# mister_case_top.net
KiCad netlist of a schematic drawn in EAGLE
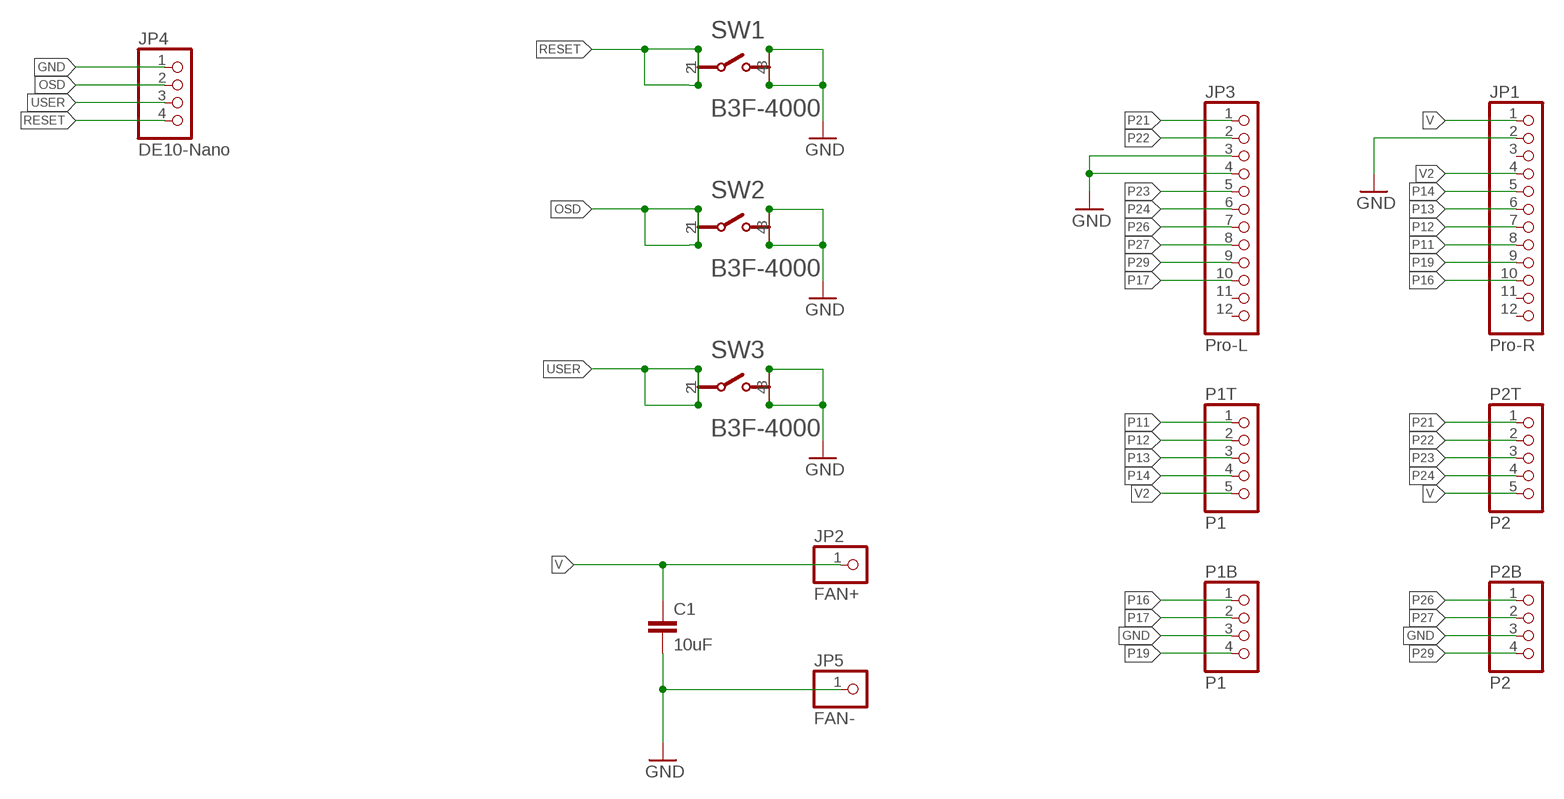
[diagram p0: schematic, sheet 1]

(export (version "E")
  (design (tool "Eeschema 10.0.6"))
  (components
    (comp (ref "C1")
      (value "10uF")
      (footprint "eagle-import:C0805")
      (libsource (lib "eagle-import") (part "C-EUC0805"))
    )
    (comp (ref "JP1")
      (value "Pro-R")
      (footprint "eagle-import:1X12L-NOHOLES")
      (libsource (lib "eagle-import") (part "PINHD-1X12-NOHOLESNOHOLES"))
    )
    (comp (ref "JP2")
      (value "FAN+")
      (footprint "eagle-import:1X01")
      (libsource (lib "eagle-import") (part "PINHD-1X1"))
    )
    (comp (ref "JP3")
      (value "Pro-L")
      (footprint "eagle-import:1X12L-NOHOLES")
      (libsource (lib "eagle-import") (part "PINHD-1X12-NOHOLESNOHOLES"))
    )
    (comp (ref "JP4")
      (value "DE10-Nano")
      (footprint "eagle-import:1X04")
      (libsource (lib "eagle-import") (part "PINHD-1X4"))
    )
    (comp (ref "JP5")
      (value "FAN-")
      (footprint "eagle-import:1X01")
      (libsource (lib "eagle-import") (part "PINHD-1X1"))
    )
    (comp (ref "P1B")
      (value "P1")
      (footprint "eagle-import:1X04")
      (libsource (lib "eagle-import") (part "pinhead_325_PINHD-1X4"))
    )
    (comp (ref "P1T")
      (value "P1")
      (footprint "eagle-import:1X05")
      (libsource (lib "eagle-import") (part "PINHD-1X5"))
    )
    (comp (ref "P2B")
      (value "P2")
      (footprint "eagle-import:1X04")
      (libsource (lib "eagle-import") (part "pinhead_325_PINHD-1X4"))
    )
    (comp (ref "P2T")
      (value "P2")
      (footprint "eagle-import:1X05")
      (libsource (lib "eagle-import") (part "PINHD-1X5"))
    )
    (comp (ref "SW1")
      (value "OMRON_B3F-4000")
      (footprint "eagle-import:OMRON_B3F-4000_NOHOLES")
      (libsource (lib "eagle-import") (part "OMRON_B3F-4000"))
    )
    (comp (ref "SW2")
      (value "OMRON_B3F-4000")
      (footprint "eagle-import:OMRON_B3F-4000_NOHOLES")
      (libsource (lib "eagle-import") (part "OMRON_B3F-4000"))
    )
    (comp (ref "SW3")
      (value "OMRON_B3F-4000")
      (footprint "eagle-import:OMRON_B3F-4000_NOHOLES")
      (libsource (lib "eagle-import") (part "OMRON_B3F-4000"))
    )
  )
  (nets
    (net (code "1") (name "GND") (class "Default")
      (node (ref "C1") (pin "2") (pinfunction "2_2") (pintype "passive"))
      (node (ref "JP1") (pin "2") (pinfunction "2_2") (pintype "passive"))
      (node (ref "JP3") (pin "3") (pinfunction "3_3") (pintype "passive"))
      (node (ref "JP3") (pin "4") (pinfunction "4_4") (pintype "passive"))
      (node (ref "JP4") (pin "1") (pinfunction "1_1") (pintype "passive"))
      (node (ref "JP5") (pin "1") (pinfunction "1_1") (pintype "passive"))
      (node (ref "P1B") (pin "3") (pinfunction "3_3") (pintype "passive"))
      (node (ref "P2B") (pin "3") (pinfunction "3_3") (pintype "passive"))
      (node (ref "SW1") (pin "3") (pinfunction "3_3") (pintype "passive"))
      (node (ref "SW1") (pin "4") (pinfunction "4_4") (pintype "passive"))
      (node (ref "SW2") (pin "3") (pinfunction "3_3") (pintype "passive"))
      (node (ref "SW2") (pin "4") (pinfunction "4_4") (pintype "passive"))
      (node (ref "SW3") (pin "3") (pinfunction "3_3") (pintype "passive"))
      (node (ref "SW3") (pin "4") (pinfunction "4_4") (pintype "passive"))
    )
    (net (code "2") (name "OSD") (class "Default")
      (node (ref "JP4") (pin "2") (pinfunction "2_2") (pintype "passive"))
      (node (ref "SW2") (pin "1") (pinfunction "1_1") (pintype "passive"))
      (node (ref "SW2") (pin "2") (pinfunction "2_2") (pintype "passive"))
    )
    (net (code "3") (name "P11") (class "Default")
      (node (ref "JP1") (pin "8") (pinfunction "8_8") (pintype "passive"))
      (node (ref "P1T") (pin "1") (pinfunction "1_1") (pintype "passive"))
    )
    (net (code "4") (name "P12") (class "Default")
      (node (ref "JP1") (pin "7") (pinfunction "7_7") (pintype "passive"))
      (node (ref "P1T") (pin "2") (pinfunction "2_2") (pintype "passive"))
    )
    (net (code "5") (name "P13") (class "Default")
      (node (ref "JP1") (pin "6") (pinfunction "6_6") (pintype "passive"))
      (node (ref "P1T") (pin "3") (pinfunction "3_3") (pintype "passive"))
    )
    (net (code "6") (name "P14") (class "Default")
      (node (ref "JP1") (pin "5") (pinfunction "5_5") (pintype "passive"))
      (node (ref "P1T") (pin "4") (pinfunction "4_4") (pintype "passive"))
    )
    (net (code "7") (name "P16") (class "Default")
      (node (ref "JP1") (pin "10") (pinfunction "10_10") (pintype "passive"))
      (node (ref "P1B") (pin "1") (pinfunction "1_1") (pintype "passive"))
    )
    (net (code "8") (name "P17") (class "Default")
      (node (ref "JP3") (pin "10") (pinfunction "10_10") (pintype "passive"))
      (node (ref "P1B") (pin "2") (pinfunction "2_2") (pintype "passive"))
    )
    (net (code "9") (name "P19") (class "Default")
      (node (ref "JP1") (pin "9") (pinfunction "9_9") (pintype "passive"))
      (node (ref "P1B") (pin "4") (pinfunction "4_4") (pintype "passive"))
    )
    (net (code "10") (name "P21") (class "Default")
      (node (ref "JP3") (pin "1") (pinfunction "1_1") (pintype "passive"))
      (node (ref "P2T") (pin "1") (pinfunction "1_1") (pintype "passive"))
    )
    (net (code "11") (name "P22") (class "Default")
      (node (ref "JP3") (pin "2") (pinfunction "2_2") (pintype "passive"))
      (node (ref "P2T") (pin "2") (pinfunction "2_2") (pintype "passive"))
    )
    (net (code "12") (name "P23") (class "Default")
      (node (ref "JP3") (pin "5") (pinfunction "5_5") (pintype "passive"))
      (node (ref "P2T") (pin "3") (pinfunction "3_3") (pintype "passive"))
    )
    (net (code "13") (name "P24") (class "Default")
      (node (ref "JP3") (pin "6") (pinfunction "6_6") (pintype "passive"))
      (node (ref "P2T") (pin "4") (pinfunction "4_4") (pintype "passive"))
    )
    (net (code "14") (name "P26") (class "Default")
      (node (ref "JP3") (pin "7") (pinfunction "7_7") (pintype "passive"))
      (node (ref "P2B") (pin "1") (pinfunction "1_1") (pintype "passive"))
    )
    (net (code "15") (name "P27") (class "Default")
      (node (ref "JP3") (pin "8") (pinfunction "8_8") (pintype "passive"))
      (node (ref "P2B") (pin "2") (pinfunction "2_2") (pintype "passive"))
    )
    (net (code "16") (name "P29") (class "Default")
      (node (ref "JP3") (pin "9") (pinfunction "9_9") (pintype "passive"))
      (node (ref "P2B") (pin "4") (pinfunction "4_4") (pintype "passive"))
    )
    (net (code "17") (name "RESET") (class "Default")
      (node (ref "JP4") (pin "4") (pinfunction "4_4") (pintype "passive"))
      (node (ref "SW1") (pin "1") (pinfunction "1_1") (pintype "passive"))
      (node (ref "SW1") (pin "2") (pinfunction "2_2") (pintype "passive"))
    )
    (net (code "18") (name "USER") (class "Default")
      (node (ref "JP4") (pin "3") (pinfunction "3_3") (pintype "passive"))
      (node (ref "SW3") (pin "1") (pinfunction "1_1") (pintype "passive"))
      (node (ref "SW3") (pin "2") (pinfunction "2_2") (pintype "passive"))
    )
    (net (code "19") (name "V") (class "Default")
      (node (ref "C1") (pin "1") (pinfunction "1_1") (pintype "passive"))
      (node (ref "JP1") (pin "1") (pinfunction "1_1") (pintype "passive"))
      (node (ref "JP2") (pin "1") (pinfunction "1_1") (pintype "passive"))
      (node (ref "P2T") (pin "5") (pinfunction "5_5") (pintype "passive"))
    )
    (net (code "20") (name "V2") (class "Default")
      (node (ref "JP1") (pin "4") (pinfunction "4_4") (pintype "passive"))
      (node (ref "P1T") (pin "5") (pinfunction "5_5") (pintype "passive"))
    )
    (net (code "21") (name "unconnected-(JP1-Pad3)") (class "Default")
      (node (ref "JP1") (pin "3") (pinfunction "3_3") (pintype "passive"))
    )
    (net (code "22") (name "unconnected-(JP1-Pad11)") (class "Default")
      (node (ref "JP1") (pin "11") (pinfunction "11_11") (pintype "passive"))
    )
    (net (code "23") (name "unconnected-(JP1-Pad12)") (class "Default")
      (node (ref "JP1") (pin "12") (pinfunction "12_12") (pintype "passive"))
    )
    (net (code "24") (name "unconnected-(JP3-Pad11)") (class "Default")
      (node (ref "JP3") (pin "11") (pinfunction "11_11") (pintype "passive"))
    )
    (net (code "25") (name "unconnected-(JP3-Pad12)") (class "Default")
      (node (ref "JP3") (pin "12") (pinfunction "12_12") (pintype "passive"))
    )
  )
)
